# p3_intf_conn_pwr.net
KiCad netlist of a schematic drawn in Altium Designer
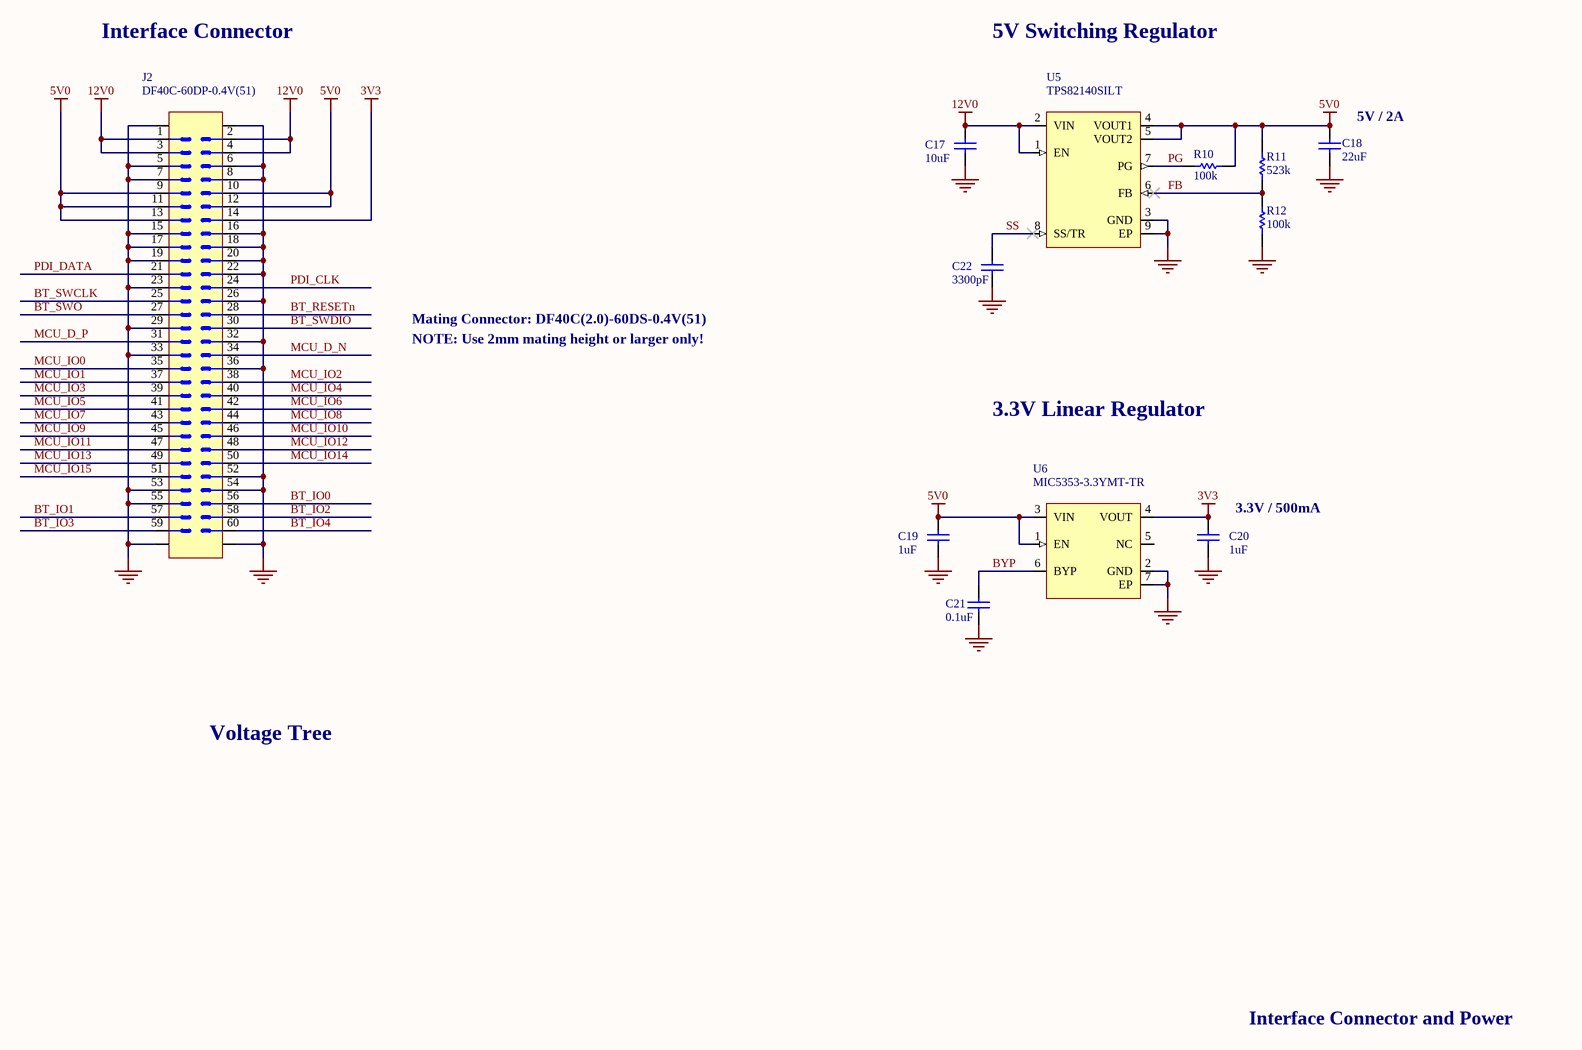
[diagram p0: p3_intf_conn_pwr.SchDoc]

(export (version "E")
  (design (tool "Eeschema 10.0.6"))
  (components
    (comp (ref "C17")
      (value "10uF")
      (footprint "C0603")
      (description "CAP CER 10UF 25V X5R 0603")
      (fields
        (field (name "MANUFACTURER") "Murata")
        (field (name "MANUFACTURER PART NUMBER") "GRM188R61E106MA73D")
      )
      (libsource (lib "Capacitors") (part "10uF 25V 0603"))
    )
    (comp (ref "C18")
      (value "22uF")
      (footprint "C0603")
      (description "CAP CER 22UF 16V X5R 0603")
      (fields
        (field (name "MANUFACTURER") "Samsung")
        (field (name "MANUFACTURER PART NUMBER") "CL10A226MO7JZNC")
      )
      (libsource (lib "Capacitors") (part "22uF 16V 0603"))
    )
    (comp (ref "C19")
      (value "1uF")
      (footprint "C0402")
      (description "CAP CER 1UF 25V X5R 0402")
      (fields
        (field (name "MANUFACTURER") "Taiyo Yuden")
        (field (name "MANUFACTURER PART NUMBER") "TMK105BJ105MV-F")
      )
      (libsource (lib "Capacitors") (part "1uF 25V 0402"))
    )
    (comp (ref "C20")
      (value "1uF")
      (footprint "C0402")
      (description "CAP CER 1UF 25V X5R 0402")
      (fields
        (field (name "MANUFACTURER") "Taiyo Yuden")
        (field (name "MANUFACTURER PART NUMBER") "TMK105BJ105MV-F")
      )
      (libsource (lib "Capacitors") (part "1uF 25V 0402"))
    )
    (comp (ref "C21")
      (value "0.1uF")
      (footprint "C0201")
      (description "CAP CER 0.1UF 16V X5R 0201")
      (fields
        (field (name "MANUFACTURER") "Murata")
        (field (name "MANUFACTURER PART NUMBER") "GRM033R61C104ME84D")
      )
      (libsource (lib "Capacitors") (part "0.1uF 16V 0201"))
    )
    (comp (ref "C22")
      (value "3300pF")
      (footprint "C0201")
      (description "CAP CER 3300PF 16V X7R 0201")
      (fields
        (field (name "MANUFACTURER") "Murata")
        (field (name "MANUFACTURER PART NUMBER") "GRM033R71C332KA88D")
      )
      (libsource (lib "Capacitors") (part "3300pF 16V 0201"))
    )
    (comp (ref "J2")
      (value "DF40C-60DP-0.4V(51)")
      (footprint "HRS_DF40C_60P_PLG")
      (description "CONN HDR 60POS 0.4MM SMD GOLD")
      (fields (field (name "MANUFACTURER") "Hirose"))
      (libsource (lib "Connectors") (part "60P 0.4mm Hirose Conn Plug"))
    )
    (comp (ref "R10")
      (value "100k")
      (footprint "R0201")
      (description "RES SMD 100K OHM 1% 1/20W 0201")
      (fields
        (field (name "MANUFACTURER") "Panasonic ECG")
        (field (name "MANUFACTURER PART NUMBER") "ERJ-1GEF1003C")
      )
      (libsource (lib "Resistors") (part "100k 0201"))
    )
    (comp (ref "R11")
      (value "523k")
      (footprint "R0201")
      (description "RES SMD 523K OHM 1% 1/20W 0201")
      (fields
        (field (name "MANUFACTURER") "Panasonic ECG")
        (field (name "MANUFACTURER PART NUMBER") "ERJ-1GEF5233C")
      )
      (libsource (lib "Resistors") (part "523k 0201"))
    )
    (comp (ref "R12")
      (value "100k")
      (footprint "R0201")
      (description "RES SMD 100K OHM 1% 1/20W 0201")
      (fields
        (field (name "MANUFACTURER") "Panasonic ECG")
        (field (name "MANUFACTURER PART NUMBER") "ERJ-1GEF1003C")
      )
      (libsource (lib "Resistors") (part "100k 0201"))
    )
    (comp (ref "U5")
      (value "TPS82140SILT")
      (footprint "TI_USIL8_SIL0008D")
      (description "STEP-DOWN CONVERTER MICROSIP")
      (fields (field (name "MANUFACTURER") "Texas Instruments"))
      (libsource (lib "ICs") (part "TPS82140SILT"))
    )
    (comp (ref "U6")
      (value "MIC5353-3.3YMT-TR")
      (footprint "MCP_MLF6_MT")
      (description "IC REG LINEAR 3.3V 500MA 6TMLF")
      (fields (field (name "MANUFACTURER") "Microchip"))
      (libsource (lib "ICs") (part "MIC5353-3.3YMT-TR"))
    )
  )
  (nets
    (net (code "1") (name "/BT_IO0") (class "Default")
      (node (ref "J2") (pin "56") (pinfunction "56_56") (pintype "passive"))
    )
    (net (code "2") (name "/BT_IO1") (class "Default")
      (node (ref "J2") (pin "57") (pinfunction "57_57") (pintype "passive"))
    )
    (net (code "3") (name "/BT_IO2") (class "Default")
      (node (ref "J2") (pin "58") (pinfunction "58_58") (pintype "passive"))
    )
    (net (code "4") (name "/BT_IO3") (class "Default")
      (node (ref "J2") (pin "59") (pinfunction "59_59") (pintype "passive"))
    )
    (net (code "5") (name "/BT_IO4") (class "Default")
      (node (ref "J2") (pin "60") (pinfunction "60_60") (pintype "passive"))
    )
    (net (code "6") (name "/BT_RESETn") (class "Default")
      (node (ref "J2") (pin "28") (pinfunction "28_28") (pintype "passive"))
    )
    (net (code "7") (name "/BT_SWCLK") (class "Default")
      (node (ref "J2") (pin "25") (pinfunction "25_25") (pintype "passive"))
    )
    (net (code "8") (name "/BT_SWDIO") (class "Default")
      (node (ref "J2") (pin "30") (pinfunction "30_30") (pintype "passive"))
    )
    (net (code "9") (name "/BT_SWO") (class "Default")
      (node (ref "J2") (pin "27") (pinfunction "27_27") (pintype "passive"))
    )
    (net (code "10") (name "/BYP") (class "Default")
      (node (ref "C21") (pin "2") (pinfunction "2_2") (pintype "passive"))
      (node (ref "U6") (pin "6") (pinfunction "BYP_6") (pintype "power_in"))
    )
    (net (code "11") (name "/FB") (class "Default")
      (node (ref "R11") (pin "1") (pinfunction "1_1") (pintype "passive"))
      (node (ref "R12") (pin "2") (pinfunction "2_2") (pintype "passive"))
      (node (ref "U5") (pin "6") (pinfunction "FB_6") (pintype "input"))
    )
    (net (code "12") (name "/MCU_D_N") (class "Default")
      (node (ref "J2") (pin "34") (pinfunction "34_34") (pintype "passive"))
    )
    (net (code "13") (name "/MCU_D_P") (class "Default")
      (node (ref "J2") (pin "31") (pinfunction "31_31") (pintype "passive"))
    )
    (net (code "14") (name "/MCU_IO0") (class "Default")
      (node (ref "J2") (pin "35") (pinfunction "35_35") (pintype "passive"))
    )
    (net (code "15") (name "/MCU_IO1") (class "Default")
      (node (ref "J2") (pin "37") (pinfunction "37_37") (pintype "passive"))
    )
    (net (code "16") (name "/MCU_IO2") (class "Default")
      (node (ref "J2") (pin "38") (pinfunction "38_38") (pintype "passive"))
    )
    (net (code "17") (name "/MCU_IO3") (class "Default")
      (node (ref "J2") (pin "39") (pinfunction "39_39") (pintype "passive"))
    )
    (net (code "18") (name "/MCU_IO4") (class "Default")
      (node (ref "J2") (pin "40") (pinfunction "40_40") (pintype "passive"))
    )
    (net (code "19") (name "/MCU_IO5") (class "Default")
      (node (ref "J2") (pin "41") (pinfunction "41_41") (pintype "passive"))
    )
    (net (code "20") (name "/MCU_IO6") (class "Default")
      (node (ref "J2") (pin "42") (pinfunction "42_42") (pintype "passive"))
    )
    (net (code "21") (name "/MCU_IO7") (class "Default")
      (node (ref "J2") (pin "43") (pinfunction "43_43") (pintype "passive"))
    )
    (net (code "22") (name "/MCU_IO8") (class "Default")
      (node (ref "J2") (pin "44") (pinfunction "44_44") (pintype "passive"))
    )
    (net (code "23") (name "/MCU_IO9") (class "Default")
      (node (ref "J2") (pin "45") (pinfunction "45_45") (pintype "passive"))
    )
    (net (code "24") (name "/MCU_IO10") (class "Default")
      (node (ref "J2") (pin "46") (pinfunction "46_46") (pintype "passive"))
    )
    (net (code "25") (name "/MCU_IO11") (class "Default")
      (node (ref "J2") (pin "47") (pinfunction "47_47") (pintype "passive"))
    )
    (net (code "26") (name "/MCU_IO12") (class "Default")
      (node (ref "J2") (pin "48") (pinfunction "48_48") (pintype "passive"))
    )
    (net (code "27") (name "/MCU_IO13") (class "Default")
      (node (ref "J2") (pin "49") (pinfunction "49_49") (pintype "passive"))
    )
    (net (code "28") (name "/MCU_IO14") (class "Default")
      (node (ref "J2") (pin "50") (pinfunction "50_50") (pintype "passive"))
    )
    (net (code "29") (name "/MCU_IO15") (class "Default")
      (node (ref "J2") (pin "51") (pinfunction "51_51") (pintype "passive"))
    )
    (net (code "30") (name "/PDI_CLK") (class "Default")
      (node (ref "J2") (pin "24") (pinfunction "24_24") (pintype "passive"))
    )
    (net (code "31") (name "/PDI_DATA") (class "Default")
      (node (ref "J2") (pin "21") (pinfunction "21_21") (pintype "passive"))
    )
    (net (code "32") (name "/PG") (class "Default")
      (node (ref "R10") (pin "1") (pinfunction "1_1") (pintype "passive"))
      (node (ref "U5") (pin "7") (pinfunction "PG_7") (pintype "output"))
    )
    (net (code "33") (name "/SS") (class "Default")
      (node (ref "C22") (pin "2") (pinfunction "2_2") (pintype "passive"))
      (node (ref "U5") (pin "8") (pinfunction "SS/TR_8") (pintype "input"))
    )
    (net (code "34") (name "3V3") (class "Default")
      (node (ref "C20") (pin "2") (pinfunction "2_2") (pintype "passive"))
      (node (ref "J2") (pin "14") (pinfunction "14_14") (pintype "passive"))
      (node (ref "U6") (pin "4") (pinfunction "VOUT_4") (pintype "power_in"))
    )
    (net (code "35") (name "5V0") (class "Default")
      (node (ref "C18") (pin "2") (pinfunction "2_2") (pintype "passive"))
      (node (ref "C19") (pin "2") (pinfunction "2_2") (pintype "passive"))
      (node (ref "J2") (pin "10") (pinfunction "10_10") (pintype "passive"))
      (node (ref "J2") (pin "11") (pinfunction "11_11") (pintype "passive"))
      (node (ref "J2") (pin "12") (pinfunction "12_12") (pintype "passive"))
      (node (ref "J2") (pin "13") (pinfunction "13_13") (pintype "passive"))
      (node (ref "J2") (pin "9") (pinfunction "9_9") (pintype "passive"))
      (node (ref "R10") (pin "2") (pinfunction "2_2") (pintype "passive"))
      (node (ref "R11") (pin "2") (pinfunction "2_2") (pintype "passive"))
      (node (ref "U5") (pin "4") (pinfunction "VOUT1_4") (pintype "power_in"))
      (node (ref "U5") (pin "5") (pinfunction "VOUT2_5") (pintype "power_in"))
      (node (ref "U6") (pin "1") (pinfunction "EN_1") (pintype "input"))
      (node (ref "U6") (pin "3") (pinfunction "VIN_3") (pintype "power_in"))
    )
    (net (code "36") (name "12V0") (class "Default")
      (node (ref "C17") (pin "2") (pinfunction "2_2") (pintype "passive"))
      (node (ref "J2") (pin "1") (pinfunction "1_1") (pintype "passive"))
      (node (ref "J2") (pin "2") (pinfunction "2_2") (pintype "passive"))
      (node (ref "J2") (pin "3") (pinfunction "3_3") (pintype "passive"))
      (node (ref "J2") (pin "4") (pinfunction "4_4") (pintype "passive"))
      (node (ref "U5") (pin "1") (pinfunction "EN_1") (pintype "input"))
      (node (ref "U5") (pin "2") (pinfunction "VIN_2") (pintype "power_in"))
    )
    (net (code "37") (name "GND") (class "Default")
      (node (ref "C17") (pin "1") (pinfunction "1_1") (pintype "passive"))
      (node (ref "C18") (pin "1") (pinfunction "1_1") (pintype "passive"))
      (node (ref "C19") (pin "1") (pinfunction "1_1") (pintype "passive"))
      (node (ref "C20") (pin "1") (pinfunction "1_1") (pintype "passive"))
      (node (ref "C21") (pin "1") (pinfunction "1_1") (pintype "passive"))
      (node (ref "C22") (pin "1") (pinfunction "1_1") (pintype "passive"))
      (node (ref "J2") (pin "15") (pinfunction "15_15") (pintype "passive"))
      (node (ref "J2") (pin "16") (pinfunction "16_16") (pintype "passive"))
      (node (ref "J2") (pin "17") (pinfunction "17_17") (pintype "passive"))
      (node (ref "J2") (pin "18") (pinfunction "18_18") (pintype "passive"))
      (node (ref "J2") (pin "19") (pinfunction "19_19") (pintype "passive"))
      (node (ref "J2") (pin "20") (pinfunction "20_20") (pintype "passive"))
      (node (ref "J2") (pin "22") (pinfunction "22_22") (pintype "passive"))
      (node (ref "J2") (pin "23") (pinfunction "23_23") (pintype "passive"))
      (node (ref "J2") (pin "26") (pinfunction "26_26") (pintype "passive"))
      (node (ref "J2") (pin "29") (pinfunction "29_29") (pintype "passive"))
      (node (ref "J2") (pin "32") (pinfunction "32_32") (pintype "passive"))
      (node (ref "J2") (pin "33") (pinfunction "33_33") (pintype "passive"))
      (node (ref "J2") (pin "36") (pinfunction "36_36") (pintype "passive"))
      (node (ref "J2") (pin "5") (pinfunction "5_5") (pintype "passive"))
      (node (ref "J2") (pin "52") (pinfunction "52_52") (pintype "passive"))
      (node (ref "J2") (pin "53") (pinfunction "53_53") (pintype "passive"))
      (node (ref "J2") (pin "54") (pinfunction "54_54") (pintype "passive"))
      (node (ref "J2") (pin "55") (pinfunction "55_55") (pintype "passive"))
      (node (ref "J2") (pin "6") (pinfunction "6_6") (pintype "passive"))
      (node (ref "J2") (pin "61") (pinfunction "61_61") (pintype "passive"))
      (node (ref "J2") (pin "62") (pinfunction "62_62") (pintype "passive"))
      (node (ref "J2") (pin "63") (pinfunction "63_63") (pintype "passive"))
      (node (ref "J2") (pin "64") (pinfunction "64_64") (pintype "passive"))
      (node (ref "J2") (pin "7") (pinfunction "7_7") (pintype "passive"))
      (node (ref "J2") (pin "8") (pinfunction "8_8") (pintype "passive"))
      (node (ref "R12") (pin "1") (pinfunction "1_1") (pintype "passive"))
      (node (ref "U5") (pin "3") (pinfunction "GND_3") (pintype "power_in"))
      (node (ref "U5") (pin "9") (pinfunction "EP_9") (pintype "power_in"))
      (node (ref "U6") (pin "2") (pinfunction "GND_2") (pintype "power_in"))
      (node (ref "U6") (pin "7") (pinfunction "EP_7") (pintype "power_in"))
    )
    (net (code "38") (name "unconnected-(U6-NC-Pad5)") (class "Default")
      (node (ref "U6") (pin "5") (pinfunction "NC_5") (pintype "passive"))
    )
  )
)
